# COMMUNICATION.net
KiCad netlist of a schematic drawn in Altium Designer
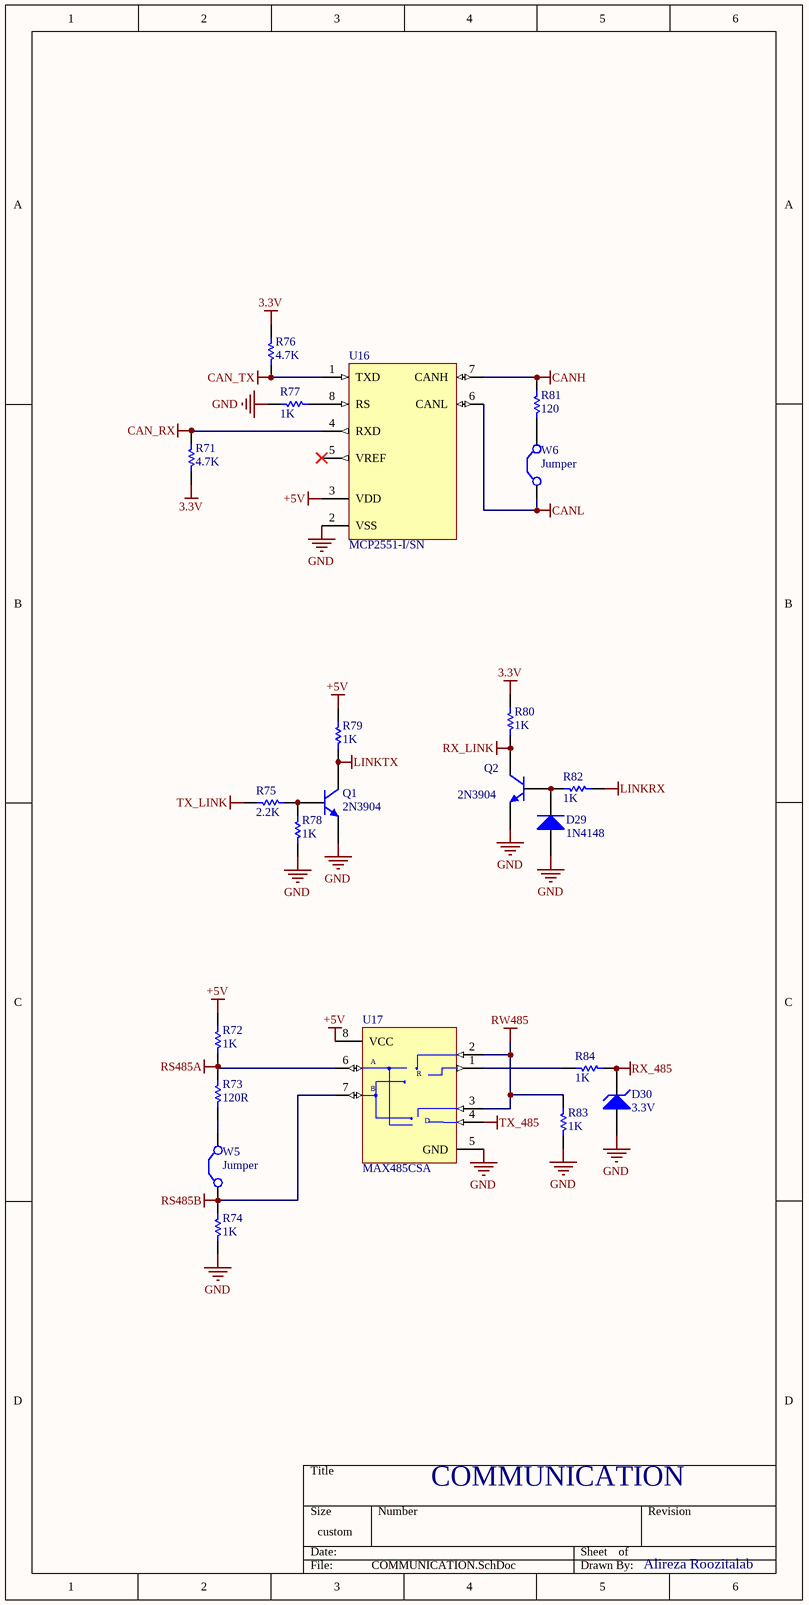
[diagram p0: COMMUNICATION.SchDoc]

(export (version "E")
  (design (tool "Eeschema 10.0.6"))
  (components
    (comp (ref "D29")
      (value "1N4148")
      (footprint "Diode-1n4148 - SMD PAD")
      (description "Default Diode")
      (fields (field (name "PUBLISHER") "Altium Limited"))
      (libsource (lib "Miscellaneous Devices") (part "Diode"))
    )
    (comp (ref "D30")
      (value "3.3V")
      (footprint "Diode-1n4148 - SMD PAD")
      (description "Zener Diode")
      (fields (field (name "PUBLISHER") "Altium Limited"))
      (libsource (lib "Miscellaneous Devices") (part "D Zener"))
    )
    (comp (ref "Q1")
      (value "2N3904")
      (footprint "2N3906_SMD")
      (description "NPN General Purpose Amplifier")
      (fields (field (name "PUBLISHER") "Altium Limited"))
      (libsource (lib "Miscellaneous Devices") (part "2N3904"))
    )
    (comp (ref "Q2")
      (value "2N3904")
      (footprint "2N3906_SMD")
      (description "NPN General Purpose Amplifier")
      (fields (field (name "PUBLISHER") "Altium Limited"))
      (libsource (lib "Miscellaneous Devices") (part "2N3904"))
    )
    (comp (ref "R71")
      (value "4.7K")
      (footprint "RES 1206 (3216X08L)")
      (description "Semiconductor Resistor")
      (fields (field (name "Comment") "Res Semi") (field (name "PUBLISHER") "Altium Limited"))
      (libsource (lib "") (part "Res Semi_1"))
    )
    (comp (ref "R72")
      (value "1K")
      (footprint "RES 1206 (3216X08L)")
      (description "Semiconductor Resistor")
      (fields (field (name "Comment") "Res Semi") (field (name "PUBLISHER") "Altium Limited"))
      (libsource (lib "") (part "Res Semi_1"))
    )
    (comp (ref "R73")
      (value "120R")
      (footprint "RES 1206 (3216X08L)")
      (description "Semiconductor Resistor")
      (fields (field (name "Comment") "Res Semi") (field (name "PUBLISHER") "Altium Limited"))
      (libsource (lib "") (part "Res Semi_1"))
    )
    (comp (ref "R74")
      (value "1K")
      (footprint "RES 1206 (3216X08L)")
      (description "Semiconductor Resistor")
      (fields (field (name "Comment") "Res Semi") (field (name "PUBLISHER") "Altium Limited"))
      (libsource (lib "") (part "Res Semi_1"))
    )
    (comp (ref "R75")
      (value "2.2K")
      (footprint "RES 1206 (3216X08L)")
      (description "Semiconductor Resistor")
      (fields (field (name "Comment") "Res Semi") (field (name "PUBLISHER") "Altium Limited"))
      (libsource (lib "Miscellaneous Devices") (part "Res Semi"))
    )
    (comp (ref "R76")
      (value "4.7K")
      (footprint "RES 1206 (3216X08L)")
      (description "Semiconductor Resistor")
      (fields (field (name "Comment") "Res Semi") (field (name "PUBLISHER") "Altium Limited"))
      (libsource (lib "") (part "Res Semi_1"))
    )
    (comp (ref "R77")
      (value "1K")
      (footprint "RES 1206 (3216X08L)")
      (description "Semiconductor Resistor")
      (fields (field (name "Comment") "Res Semi") (field (name "PUBLISHER") "Altium Limited"))
      (libsource (lib "Miscellaneous Devices") (part "Res Semi"))
    )
    (comp (ref "R78")
      (value "1K")
      (footprint "RES 1206 (3216X08L)")
      (description "Semiconductor Resistor")
      (fields (field (name "Comment") "Res Semi") (field (name "PUBLISHER") "Altium Limited"))
      (libsource (lib "") (part "Res Semi_1"))
    )
    (comp (ref "R79")
      (value "1K")
      (footprint "RES 1206 (3216X08L)")
      (description "Semiconductor Resistor")
      (fields (field (name "Comment") "Res Semi") (field (name "PUBLISHER") "Altium Limited"))
      (libsource (lib "") (part "Res Semi_1"))
    )
    (comp (ref "R80")
      (value "1K")
      (footprint "RES 1206 (3216X08L)")
      (description "Semiconductor Resistor")
      (fields (field (name "Comment") "Res Semi") (field (name "PUBLISHER") "Altium Limited"))
      (libsource (lib "") (part "Res Semi_1"))
    )
    (comp (ref "R81")
      (value "120")
      (footprint "RES 1206 (3216X08L)")
      (description "Semiconductor Resistor")
      (fields (field (name "Comment") "Res Semi") (field (name "PUBLISHER") "Altium Limited"))
      (libsource (lib "") (part "Res Semi_1"))
    )
    (comp (ref "R82")
      (value "1K")
      (footprint "RES 1206 (3216X08L)")
      (description "Semiconductor Resistor")
      (fields (field (name "Comment") "Res Semi") (field (name "PUBLISHER") "Altium Limited"))
      (libsource (lib "Miscellaneous Devices") (part "Res Semi"))
    )
    (comp (ref "R83")
      (value "1K")
      (footprint "RES 1206 (3216X08L)")
      (description "Semiconductor Resistor")
      (fields (field (name "Comment") "Res Semi") (field (name "PUBLISHER") "Altium Limited"))
      (libsource (lib "") (part "Res Semi_1"))
    )
    (comp (ref "R84")
      (value "1K")
      (footprint "RES 1206 (3216X08L)")
      (description "Semiconductor Resistor")
      (fields (field (name "Comment") "Res Semi") (field (name "PUBLISHER") "Altium Limited"))
      (libsource (lib "") (part "Res Semi_1"))
    )
    (comp (ref "U16")
      (value "MCP2551-I/SN")
      (footprint "SOP8")
      (description "High-Speed CAN Transceiver, 8-Pin SOIC, Industrial Temperature")
      (fields (field (name "MANUFACTURER") "Microchip"))
      (libsource (lib "Microchip Interface") (part "MCP2551-I/SN"))
    )
    (comp (ref "U17")
      (value "MAX485CSA")
      (footprint "SOP8")
      (description "Low-Power, Slew-Rate-Limited RS-485/RS-422 Transceiver")
      (fields (field (name "PUBLISHER") "Altium Limited"))
      (libsource (lib "Maxim Communication Transceiver") (part "MAX485CSA"))
    )
    (comp (ref "W5")
      (value "Jumper")
      (footprint "RES 0402 (1005X04L)")
      (description "Jumper Wire")
      (fields (field (name "PUBLISHER") "Altium Limited"))
      (libsource (lib "Miscellaneous Devices") (part "Jumper"))
    )
    (comp (ref "W6")
      (value "Jumper")
      (footprint "RES 0402 (1005X04L)")
      (description "Jumper Wire")
      (fields (field (name "PUBLISHER") "Altium Limited"))
      (libsource (lib "Miscellaneous Devices") (part "Jumper"))
    )
  )
  (nets
    (net (code "1") (name "+5V") (class "Default")
      (node (ref "R72") (pin "2") (pinfunction "2_2") (pintype "passive"))
      (node (ref "R79") (pin "1") (pinfunction "1_1") (pintype "passive"))
      (node (ref "U16") (pin "3") (pinfunction "VDD_3") (pintype "power_in"))
      (node (ref "U17") (pin "8") (pinfunction "VCC_8") (pintype "power_in"))
    )
    (net (code "2") (name "3.3V") (class "Default")
      (node (ref "R71") (pin "2") (pinfunction "2_2") (pintype "passive"))
      (node (ref "R76") (pin "1") (pinfunction "1_1") (pintype "passive"))
      (node (ref "R80") (pin "1") (pinfunction "1_1") (pintype "passive"))
    )
    (net (code "3") (name "CANH") (class "Default")
      (node (ref "R81") (pin "1") (pinfunction "1_1") (pintype "passive"))
      (node (ref "U16") (pin "7") (pinfunction "CANH_7") (pintype "bidirectional"))
    )
    (net (code "4") (name "CANL") (class "Default")
      (node (ref "U16") (pin "6") (pinfunction "CANL_6") (pintype "bidirectional"))
      (node (ref "W6") (pin "1") (pinfunction "C1_1") (pintype "passive"))
    )
    (net (code "5") (name "CAN_RX") (class "Default")
      (node (ref "R71") (pin "1") (pinfunction "1_1") (pintype "passive"))
      (node (ref "U16") (pin "4") (pinfunction "RXD_4") (pintype "output"))
    )
    (net (code "6") (name "CAN_TX") (class "Default")
      (node (ref "R76") (pin "2") (pinfunction "2_2") (pintype "passive"))
      (node (ref "U16") (pin "1") (pinfunction "TXD_1") (pintype "input"))
    )
    (net (code "7") (name "GND") (class "Default")
      (node (ref "D29") (pin "1") (pinfunction "A_1") (pintype "passive"))
      (node (ref "D30") (pin "1") (pinfunction "A_1") (pintype "passive"))
      (node (ref "Q1") (pin "1") (pinfunction "E_1") (pintype "passive"))
      (node (ref "Q2") (pin "1") (pinfunction "E_1") (pintype "passive"))
      (node (ref "R74") (pin "1") (pinfunction "1_1") (pintype "passive"))
      (node (ref "R77") (pin "1") (pinfunction "1_1") (pintype "passive"))
      (node (ref "R78") (pin "2") (pinfunction "2_2") (pintype "passive"))
      (node (ref "R83") (pin "1") (pinfunction "1_1") (pintype "passive"))
      (node (ref "U16") (pin "2") (pinfunction "VSS_2") (pintype "power_in"))
      (node (ref "U17") (pin "5") (pinfunction "GND_5") (pintype "power_in"))
    )
    (net (code "8") (name "LINKRX") (class "Default")
      (node (ref "R82") (pin "2") (pinfunction "2_2") (pintype "passive"))
    )
    (net (code "9") (name "LINKTX") (class "Default")
      (node (ref "Q1") (pin "3") (pinfunction "C_3") (pintype "passive"))
      (node (ref "R79") (pin "2") (pinfunction "2_2") (pintype "passive"))
    )
    (net (code "10") (name "Net-(D29-K)") (class "Default")
      (node (ref "D29") (pin "2") (pinfunction "K_2") (pintype "passive"))
      (node (ref "Q2") (pin "2") (pinfunction "B_2") (pintype "passive"))
      (node (ref "R82") (pin "1") (pinfunction "1_1") (pintype "passive"))
    )
    (net (code "11") (name "Net-(Q1-B)") (class "Default")
      (node (ref "Q1") (pin "2") (pinfunction "B_2") (pintype "passive"))
      (node (ref "R75") (pin "1") (pinfunction "1_1") (pintype "passive"))
      (node (ref "R78") (pin "1") (pinfunction "1_1") (pintype "passive"))
    )
    (net (code "12") (name "Net-(U16-RS)") (class "Default")
      (node (ref "R77") (pin "2") (pinfunction "2_2") (pintype "passive"))
      (node (ref "U16") (pin "8") (pinfunction "RS_8") (pintype "input"))
    )
    (net (code "13") (name "Net-(U17-RO)") (class "Default")
      (node (ref "R84") (pin "2") (pinfunction "2_2") (pintype "passive"))
      (node (ref "U17") (pin "1") (pinfunction "RO_1") (pintype "output"))
    )
    (net (code "14") (name "Net-(W5-C2)") (class "Default")
      (node (ref "R73") (pin "1") (pinfunction "1_1") (pintype "passive"))
      (node (ref "W5") (pin "2") (pinfunction "C2_2") (pintype "passive"))
    )
    (net (code "15") (name "Net-(W6-C2)") (class "Default")
      (node (ref "R81") (pin "2") (pinfunction "2_2") (pintype "passive"))
      (node (ref "W6") (pin "2") (pinfunction "C2_2") (pintype "passive"))
    )
    (net (code "16") (name "RS485A") (class "Default")
      (node (ref "R72") (pin "1") (pinfunction "1_1") (pintype "passive"))
      (node (ref "R73") (pin "2") (pinfunction "2_2") (pintype "passive"))
      (node (ref "U17") (pin "6") (pinfunction "A_6") (pintype "bidirectional"))
    )
    (net (code "17") (name "RS485B") (class "Default")
      (node (ref "R74") (pin "2") (pinfunction "2_2") (pintype "passive"))
      (node (ref "U17") (pin "7") (pinfunction "B_7") (pintype "bidirectional"))
      (node (ref "W5") (pin "1") (pinfunction "C1_1") (pintype "passive"))
    )
    (net (code "18") (name "RW485") (class "Default")
      (node (ref "R83") (pin "2") (pinfunction "2_2") (pintype "passive"))
      (node (ref "U17") (pin "2") (pinfunction "~{RE}_2") (pintype "input"))
      (node (ref "U17") (pin "3") (pinfunction "DE_3") (pintype "input"))
    )
    (net (code "19") (name "RX_485") (class "Default")
      (node (ref "D30") (pin "2") (pinfunction "K_2") (pintype "passive"))
      (node (ref "R84") (pin "1") (pinfunction "1_1") (pintype "passive"))
    )
    (net (code "20") (name "RX_LINK") (class "Default")
      (node (ref "Q2") (pin "3") (pinfunction "C_3") (pintype "passive"))
      (node (ref "R80") (pin "2") (pinfunction "2_2") (pintype "passive"))
    )
    (net (code "21") (name "TX_485") (class "Default")
      (node (ref "U17") (pin "4") (pinfunction "DI_4") (pintype "input"))
    )
    (net (code "22") (name "TX_LINK") (class "Default")
      (node (ref "R75") (pin "2") (pinfunction "2_2") (pintype "passive"))
    )
    (net (code "23") (name "unconnected-(U16-VREF-Pad5)") (class "Default")
      (node (ref "U16") (pin "5") (pinfunction "VREF_5") (pintype "output+no_connect"))
    )
  )
)
